# PCM3060_Guitar_Cape.net
KiCad netlist of a schematic drawn in EAGLE
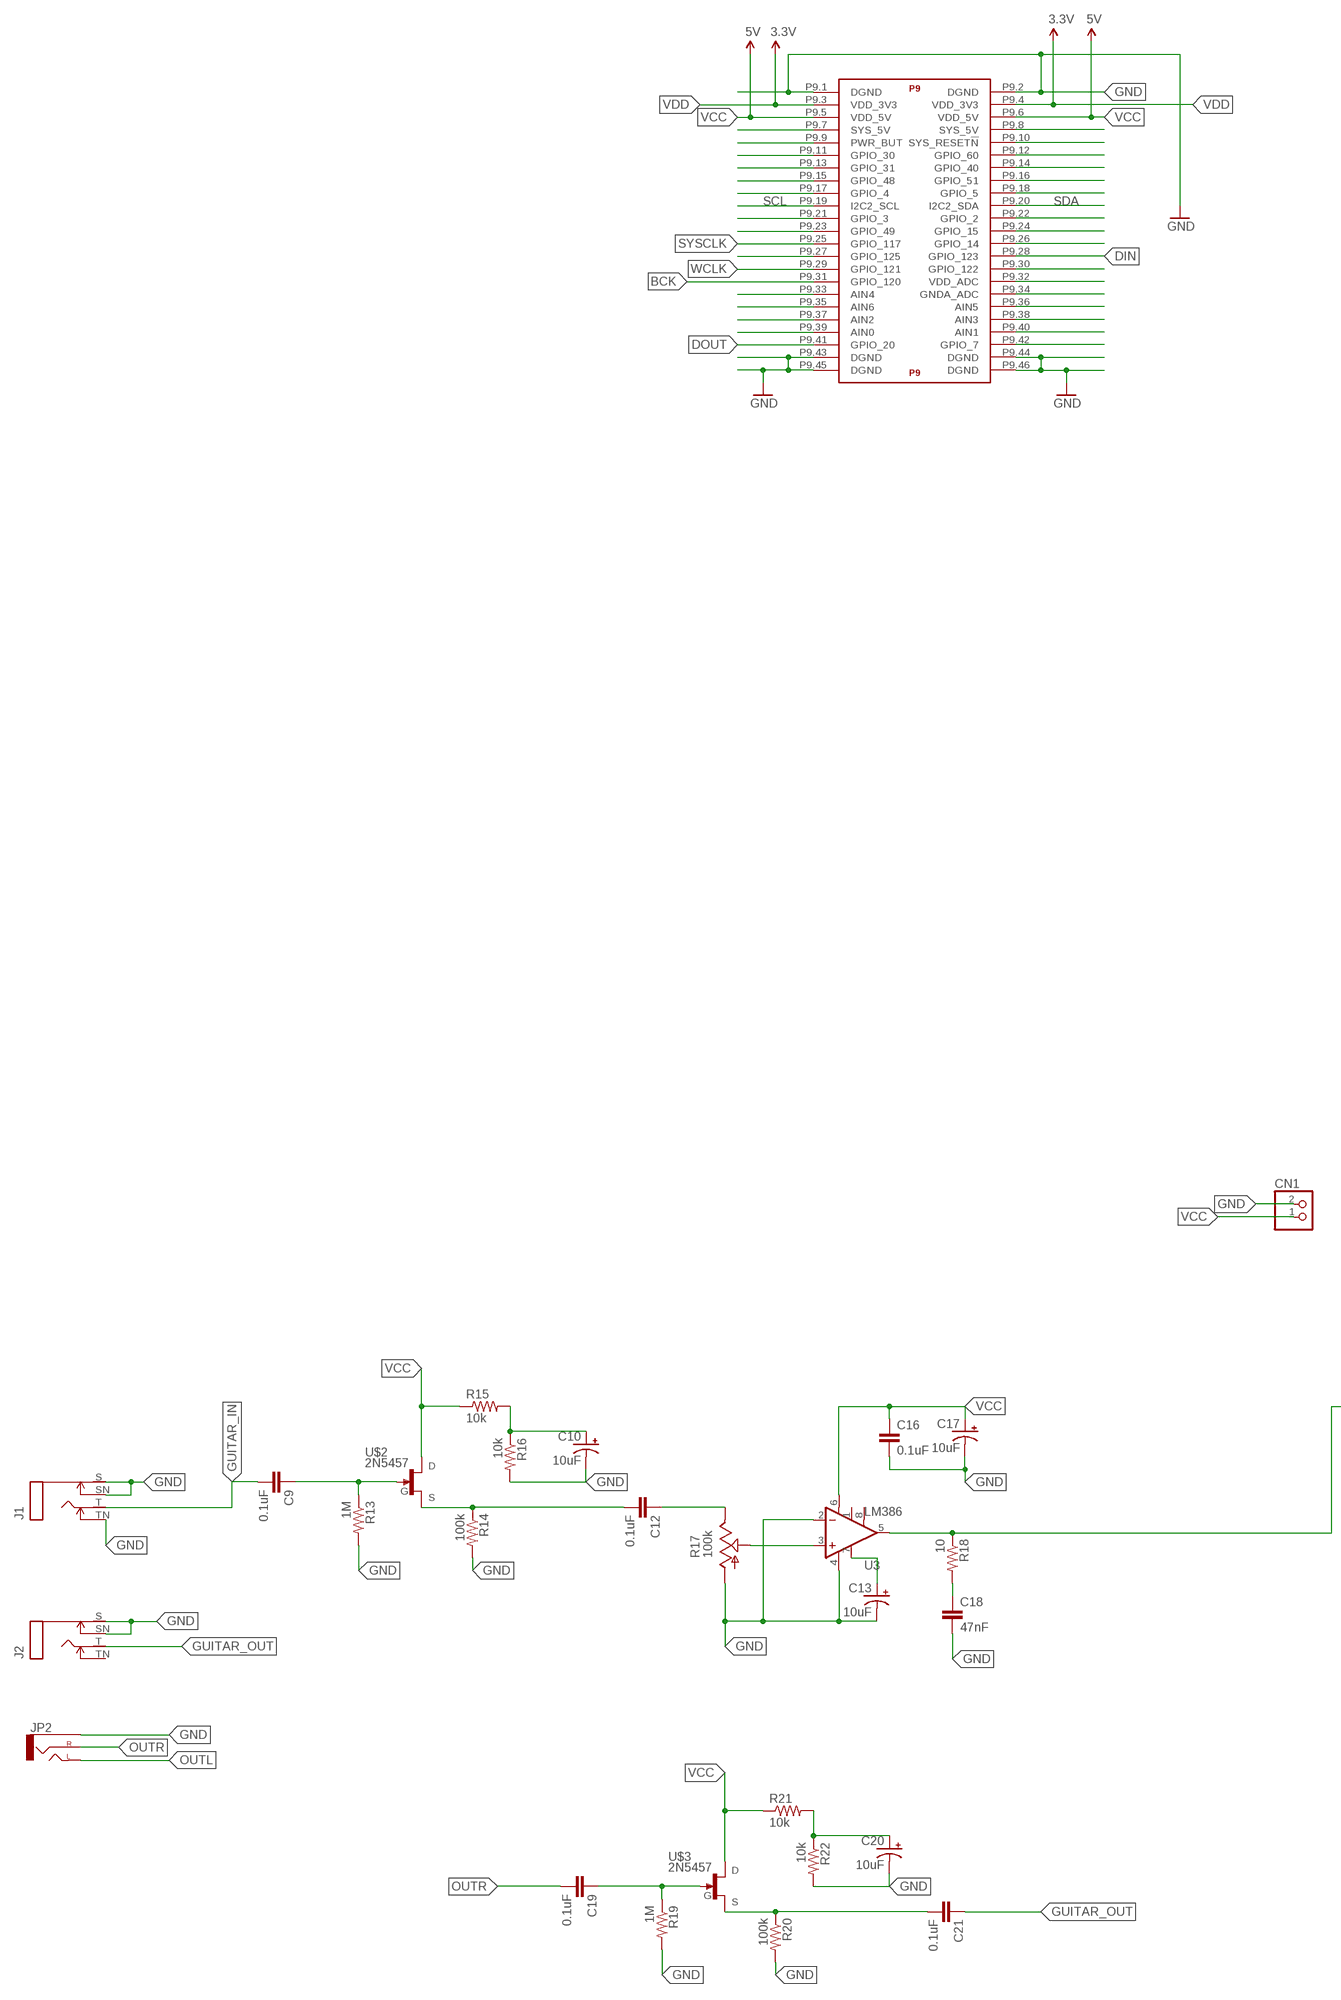
[diagram p0: schematic, sheet 1, part 1 of 2]
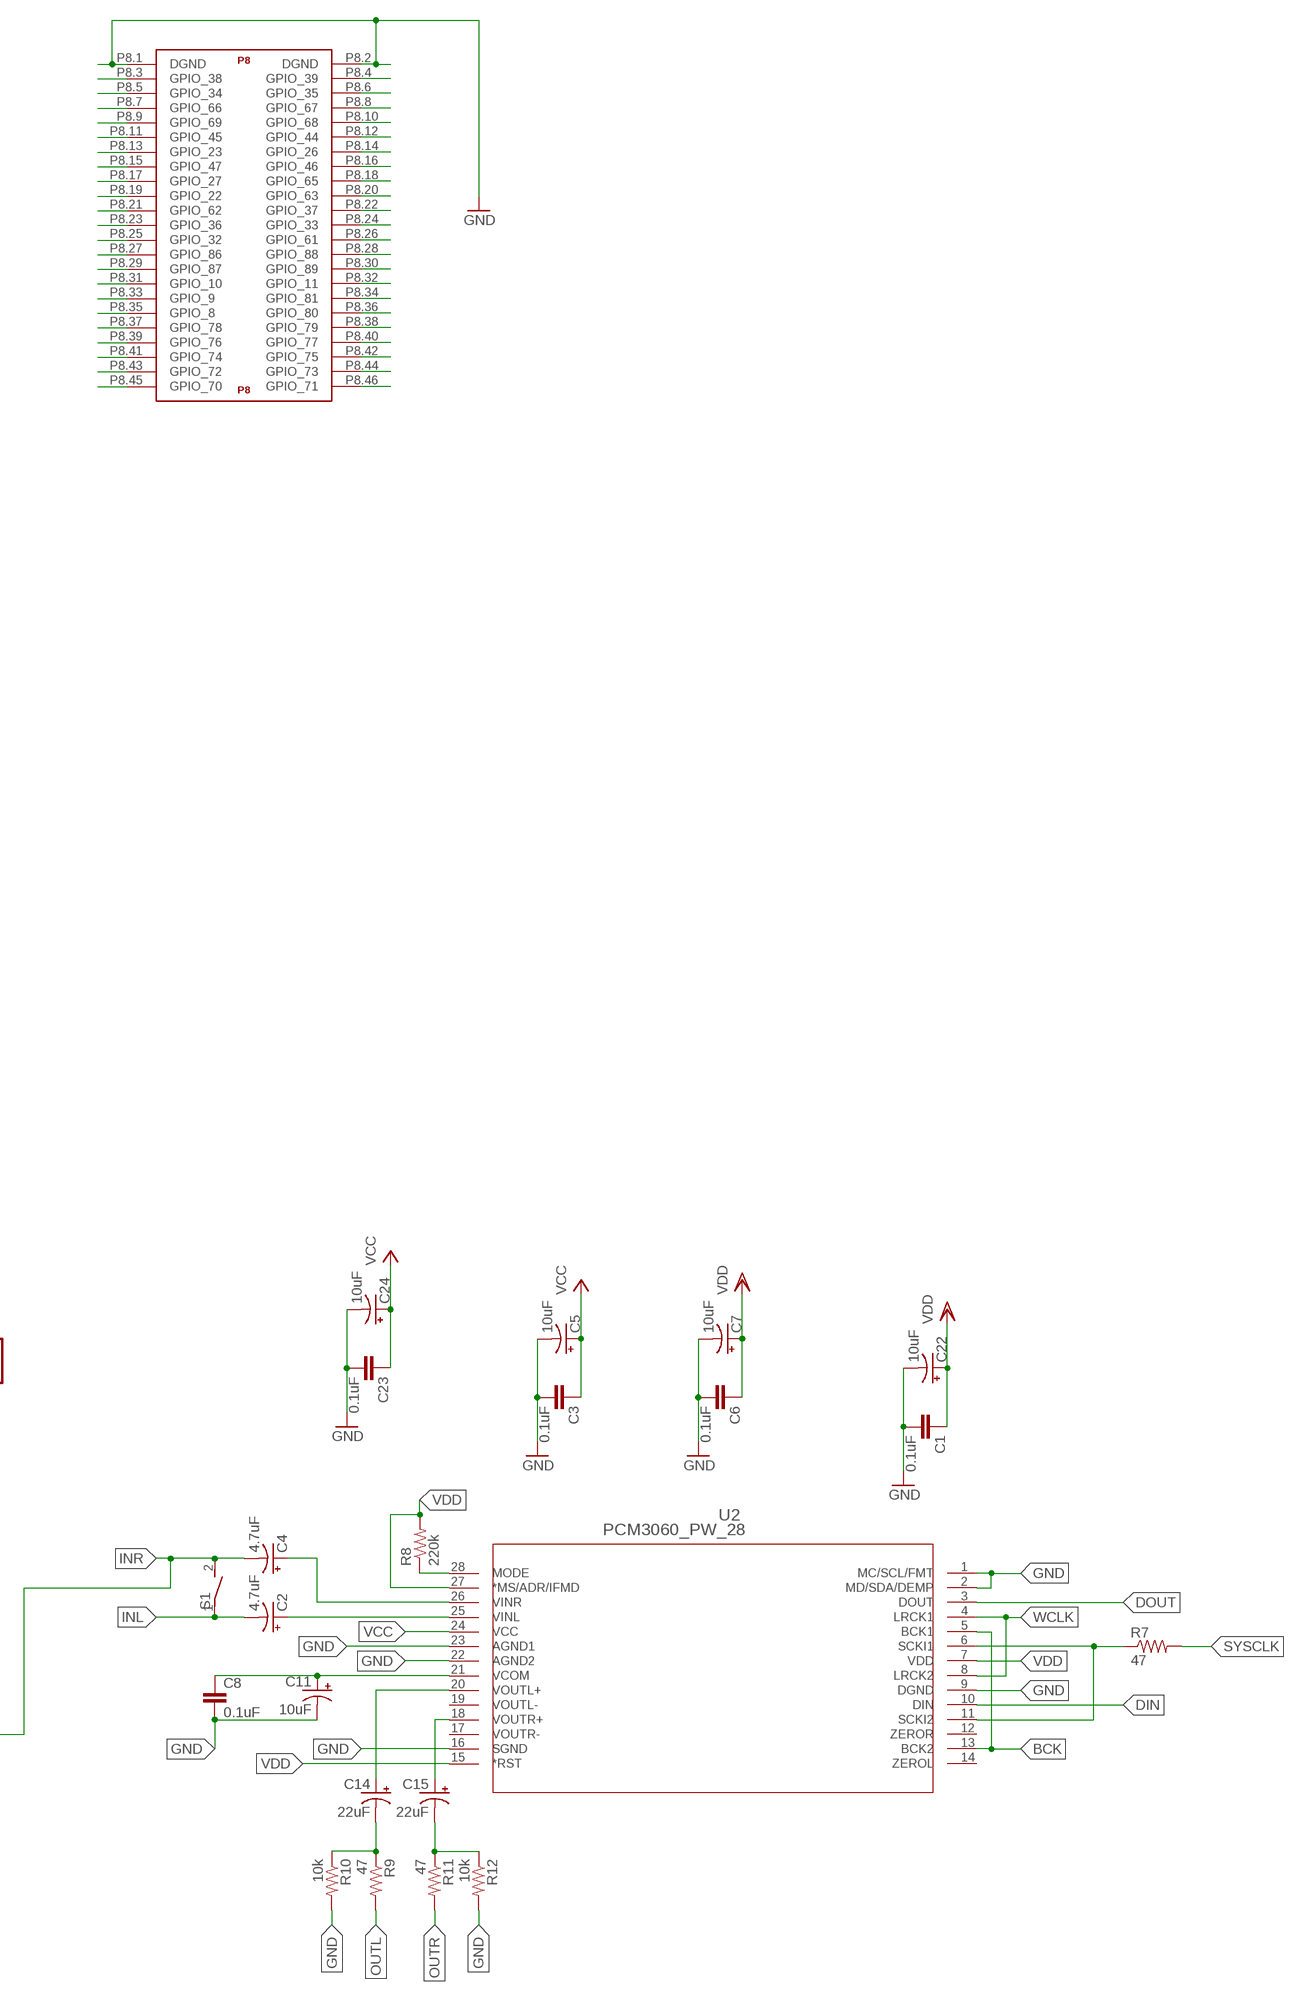
[diagram p1: schematic, sheet 1, part 2 of 2]

(export (version "E")
  (design (tool "Eeschema 10.0.6"))
  (components
    (comp (ref "C1")
      (value "0.1uF")
      (footprint "eagle-import:0603-CAP")
      (libsource (lib "eagle-import") (part "0.1UF-25V-5%(0603)"))
    )
    (comp (ref "C2")
      (value "4.7uF")
      (footprint "eagle-import:CPOL-RADIAL-10UF-25V")
      (libsource (lib "eagle-import") (part "CAP_POLPTH2"))
    )
    (comp (ref "C3")
      (value "0.1uF")
      (footprint "eagle-import:0603-CAP")
      (libsource (lib "eagle-import") (part "0.1UF-25V-5%(0603)"))
    )
    (comp (ref "C4")
      (value "4.7uF")
      (footprint "eagle-import:CPOL-RADIAL-10UF-25V")
      (libsource (lib "eagle-import") (part "CAP_POLPTH2"))
    )
    (comp (ref "C5")
      (value "10uF")
      (footprint "eagle-import:CPOL-RADIAL-10UF-25V")
      (libsource (lib "eagle-import") (part "CAP_POLPTH2"))
    )
    (comp (ref "C6")
      (value "0.1uF")
      (footprint "eagle-import:0603-CAP")
      (libsource (lib "eagle-import") (part "0.1UF-25V-5%(0603)"))
    )
    (comp (ref "C7")
      (value "10uF")
      (footprint "eagle-import:CPOL-RADIAL-10UF-25V")
      (libsource (lib "eagle-import") (part "CAP_POLPTH2"))
    )
    (comp (ref "C8")
      (value "0.1uF")
      (footprint "eagle-import:0603-CAP")
      (libsource (lib "eagle-import") (part "0.1UF-25V-5%(0603)"))
    )
    (comp (ref "C9")
      (value "0.1uF")
      (footprint "eagle-import:0603-CAP")
      (libsource (lib "eagle-import") (part "0.1UF-25V-5%(0603)"))
    )
    (comp (ref "C10")
      (value "10uF")
      (footprint "eagle-import:CPOL-RADIAL-10UF-25V")
      (libsource (lib "eagle-import") (part "CAP_POLPTH2"))
    )
    (comp (ref "C11")
      (value "10uF")
      (footprint "eagle-import:CPOL-RADIAL-10UF-25V")
      (libsource (lib "eagle-import") (part "CAP_POLPTH2"))
    )
    (comp (ref "C12")
      (value "0.1uF")
      (footprint "eagle-import:0603-CAP")
      (libsource (lib "eagle-import") (part "0.1UF-25V-5%(0603)"))
    )
    (comp (ref "C13")
      (value "10uF")
      (footprint "eagle-import:CPOL-RADIAL-10UF-25V")
      (libsource (lib "eagle-import") (part "CAP_POLPTH2"))
    )
    (comp (ref "C14")
      (value "22uF")
      (footprint "eagle-import:CPOL-RADIAL-10UF-25V")
      (libsource (lib "eagle-import") (part "CAP_POLPTH2"))
    )
    (comp (ref "C15")
      (value "22uF")
      (footprint "eagle-import:CPOL-RADIAL-10UF-25V")
      (libsource (lib "eagle-import") (part "CAP_POLPTH2"))
    )
    (comp (ref "C16")
      (value "0.1uF")
      (footprint "eagle-import:0603-CAP")
      (libsource (lib "eagle-import") (part "0.1UF-25V-5%(0603)"))
    )
    (comp (ref "C17")
      (value "10uF")
      (footprint "eagle-import:CPOL-RADIAL-10UF-25V")
      (libsource (lib "eagle-import") (part "CAP_POLPTH2"))
    )
    (comp (ref "C18")
      (value "47nF")
      (footprint "eagle-import:0603-CAP")
      (libsource (lib "eagle-import") (part "47NF(0.047UF/47000PF)-25V-5%(0603)SMD"))
    )
    (comp (ref "C19")
      (value "0.1uF")
      (footprint "eagle-import:0603-CAP")
      (libsource (lib "eagle-import") (part "0.1UF-25V-5%(0603)"))
    )
    (comp (ref "C20")
      (value "10uF")
      (footprint "eagle-import:CPOL-RADIAL-10UF-25V")
      (libsource (lib "eagle-import") (part "CAP_POLPTH2"))
    )
    (comp (ref "C21")
      (value "0.1uF")
      (footprint "eagle-import:0603-CAP")
      (libsource (lib "eagle-import") (part "0.1UF-25V-5%(0603)"))
    )
    (comp (ref "C22")
      (value "10uF")
      (footprint "eagle-import:CPOL-RADIAL-10UF-25V")
      (libsource (lib "eagle-import") (part "CAP_POLPTH2"))
    )
    (comp (ref "C23")
      (value "0.1uF")
      (footprint "eagle-import:0603-CAP")
      (libsource (lib "eagle-import") (part "0.1UF-25V-5%(0603)"))
    )
    (comp (ref "C24")
      (value "10uF")
      (footprint "eagle-import:CPOL-RADIAL-10UF-25V")
      (libsource (lib "eagle-import") (part "CAP_POLPTH2"))
    )
    (comp (ref "CN1")
      (value "JST_2PIN-THM")
      (footprint "eagle-import:JST-PH-2-THM")
      (libsource (lib "eagle-import") (part "JST_2PIN-THM"))
    )
    (comp (ref "J1")
      (value "MONOSW")
      (footprint "eagle-import:NMJ4HCD2")
      (libsource (lib "eagle-import") (part "MONOSW"))
    )
    (comp (ref "J2")
      (value "MONOSW")
      (footprint "eagle-import:NMJ4HCD2")
      (libsource (lib "eagle-import") (part "MONOSW"))
    )
    (comp (ref "JP2")
      (value "AUDIO-JACK2.5MM")
      (footprint "eagle-import:STEREOJACK2.5MM_STEREOJACK2.5MM")
      (libsource (lib "eagle-import") (part "AUDIO-JACK2.5MM"))
    )
    (comp (ref "R7")
      (value "47")
      (footprint "eagle-import:1206")
      (libsource (lib "eagle-import") (part "RESISTOR1206"))
    )
    (comp (ref "R8")
      (value "220k")
      (footprint "eagle-import:1206")
      (libsource (lib "eagle-import") (part "RESISTOR1206"))
    )
    (comp (ref "R9")
      (value "47")
      (footprint "eagle-import:1206")
      (libsource (lib "eagle-import") (part "RESISTOR1206"))
    )
    (comp (ref "R10")
      (value "10k")
      (footprint "eagle-import:1206")
      (libsource (lib "eagle-import") (part "RESISTOR1206"))
    )
    (comp (ref "R11")
      (value "47")
      (footprint "eagle-import:1206")
      (libsource (lib "eagle-import") (part "RESISTOR1206"))
    )
    (comp (ref "R12")
      (value "10k")
      (footprint "eagle-import:1206")
      (libsource (lib "eagle-import") (part "RESISTOR1206"))
    )
    (comp (ref "R13")
      (value "1M")
      (footprint "eagle-import:1206")
      (libsource (lib "eagle-import") (part "RESISTOR1206"))
    )
    (comp (ref "R14")
      (value "100k")
      (footprint "eagle-import:1206")
      (libsource (lib "eagle-import") (part "RESISTOR1206"))
    )
    (comp (ref "R15")
      (value "10k")
      (footprint "eagle-import:1206")
      (libsource (lib "eagle-import") (part "RESISTOR1206"))
    )
    (comp (ref "R16")
      (value "10k")
      (footprint "eagle-import:1206")
      (libsource (lib "eagle-import") (part "RESISTOR1206"))
    )
    (comp (ref "R17")
      (value "100k")
      (footprint "eagle-import:RJ9W")
      (libsource (lib "eagle-import") (part "TRIM_US-RJ9W"))
    )
    (comp (ref "R18")
      (value "10")
      (footprint "eagle-import:1206")
      (libsource (lib "eagle-import") (part "RESISTOR1206"))
    )
    (comp (ref "R19")
      (value "1M")
      (footprint "eagle-import:1206")
      (libsource (lib "eagle-import") (part "RESISTOR1206"))
    )
    (comp (ref "R20")
      (value "100k")
      (footprint "eagle-import:1206")
      (libsource (lib "eagle-import") (part "RESISTOR1206"))
    )
    (comp (ref "R21")
      (value "10k")
      (footprint "eagle-import:1206")
      (libsource (lib "eagle-import") (part "RESISTOR1206"))
    )
    (comp (ref "R22")
      (value "10k")
      (footprint "eagle-import:1206")
      (libsource (lib "eagle-import") (part "RESISTOR1206"))
    )
    (comp (ref "S1")
      (value "DS01E")
      (footprint "eagle-import:DS-01")
      (libsource (lib "eagle-import") (part "DS01E"))
    )
    (comp (ref "U$1")
      (value "BEAGLE_BONE_BLACK_CAPE")
      (footprint "eagle-import:BEAGLE_BONE_BLACK_CAPE")
      (libsource (lib "eagle-import") (part "BEAGLE_BONE_BLACK_CAPE"))
    )
    (comp (ref "U$2")
      (value "2N5457")
      (footprint "eagle-import:TO-92")
      (libsource (lib "eagle-import") (part "2N5457"))
    )
    (comp (ref "U$3")
      (value "2N5457")
      (footprint "eagle-import:TO-92")
      (libsource (lib "eagle-import") (part "2N5457"))
    )
    (comp (ref "U2")
      (value "PCM3060_PW_28")
      (footprint "eagle-import:PW28")
      (fields
        (field (name "GENERIC_PART_NUMBER") "PCM3060")
        (field (name "MANUFACTURER") "Texas Instruments")
        (field (name "MANUFACTURER_PART_NUMBER") "pcm3060_pw_28")
      )
      (libsource (lib "eagle-import") (part "PCM3060_PW_28"))
    )
    (comp (ref "U3")
      (value "LM386")
      (footprint "eagle-import:DIP08")
      (libsource (lib "eagle-import") (part "LM386"))
    )
  )
  (nets
    (net (code "1") (name "/SCL") (class "Default")
      (node (ref "U$1") (pin "P9.19") (pinfunction "I2C2_SCL_P9.19") (pintype "bidirectional"))
    )
    (net (code "2") (name "/SDA") (class "Default")
      (node (ref "U$1") (pin "P9.20") (pinfunction "I2C2_SDA_P9.20") (pintype "bidirectional"))
    )
    (net (code "3") (name "BCK") (class "Default")
      (node (ref "U$1") (pin "P9.31") (pinfunction "GPIO_120_P9.31") (pintype "bidirectional"))
      (node (ref "U2") (pin "13") (pinfunction "BCK2_13") (pintype "bidirectional"))
      (node (ref "U2") (pin "5") (pinfunction "BCK1_5") (pintype "bidirectional"))
    )
    (net (code "4") (name "DIN") (class "Default")
      (node (ref "U$1") (pin "P9.28") (pinfunction "GPIO_123_P9.28") (pintype "bidirectional"))
      (node (ref "U2") (pin "10") (pinfunction "DIN_10") (pintype "input"))
    )
    (net (code "5") (name "DOUT") (class "Default")
      (node (ref "U$1") (pin "P9.41") (pinfunction "GPIO_20_P9.41") (pintype "bidirectional"))
      (node (ref "U2") (pin "3") (pinfunction "DOUT_3") (pintype "output"))
    )
    (net (code "6") (name "GND") (class "Default")
      (node (ref "C1") (pin "2") (pinfunction "2_2") (pintype "passive"))
      (node (ref "C10") (pin "2") (pinfunction "-_2") (pintype "passive"))
      (node (ref "C11") (pin "2") (pinfunction "-_2") (pintype "passive"))
      (node (ref "C13") (pin "2") (pinfunction "-_2") (pintype "passive"))
      (node (ref "C16") (pin "2") (pinfunction "2_2") (pintype "passive"))
      (node (ref "C17") (pin "2") (pinfunction "-_2") (pintype "passive"))
      (node (ref "C18") (pin "2") (pinfunction "2_2") (pintype "passive"))
      (node (ref "C20") (pin "2") (pinfunction "-_2") (pintype "passive"))
      (node (ref "C22") (pin "2") (pinfunction "-_2") (pintype "passive"))
      (node (ref "C23") (pin "2") (pinfunction "2_2") (pintype "passive"))
      (node (ref "C24") (pin "2") (pinfunction "-_2") (pintype "passive"))
      (node (ref "C3") (pin "2") (pinfunction "2_2") (pintype "passive"))
      (node (ref "C5") (pin "2") (pinfunction "-_2") (pintype "passive"))
      (node (ref "C6") (pin "2") (pinfunction "2_2") (pintype "passive"))
      (node (ref "C7") (pin "2") (pinfunction "-_2") (pintype "passive"))
      (node (ref "C8") (pin "2") (pinfunction "2_2") (pintype "passive"))
      (node (ref "CN1") (pin "2") (pinfunction "1_2") (pintype "passive"))
      (node (ref "J1") (pin "S") (pinfunction "S_S") (pintype "passive"))
      (node (ref "J1") (pin "SN") (pinfunction "SN_SN") (pintype "passive"))
      (node (ref "J1") (pin "TN") (pinfunction "TN_TN") (pintype "passive"))
      (node (ref "J2") (pin "S") (pinfunction "S_S") (pintype "passive"))
      (node (ref "J2") (pin "SN") (pinfunction "SN_SN") (pintype "passive"))
      (node (ref "JP2") (pin "RING1") (pinfunction "SLEEVE_RING1") (pintype "bidirectional"))
      (node (ref "R10") (pin "2") (pinfunction "2_2") (pintype "passive"))
      (node (ref "R12") (pin "2") (pinfunction "2_2") (pintype "passive"))
      (node (ref "R13") (pin "2") (pinfunction "2_2") (pintype "passive"))
      (node (ref "R14") (pin "2") (pinfunction "2_2") (pintype "passive"))
      (node (ref "R16") (pin "2") (pinfunction "2_2") (pintype "passive"))
      (node (ref "R17") (pin "A") (pinfunction "A_A") (pintype "passive"))
      (node (ref "R19") (pin "2") (pinfunction "2_2") (pintype "passive"))
      (node (ref "R20") (pin "2") (pinfunction "2_2") (pintype "passive"))
      (node (ref "R22") (pin "2") (pinfunction "2_2") (pintype "passive"))
      (node (ref "U$1") (pin "P8.1") (pinfunction "DGND_P8.1") (pintype "bidirectional"))
      (node (ref "U$1") (pin "P8.2") (pinfunction "DGND_P8.2") (pintype "bidirectional"))
      (node (ref "U$1") (pin "P9.1") (pinfunction "DGND_P9.1") (pintype "bidirectional"))
      (node (ref "U$1") (pin "P9.2") (pinfunction "DGND_P9.2") (pintype "bidirectional"))
      (node (ref "U$1") (pin "P9.43") (pinfunction "DGND_P9.43") (pintype "bidirectional"))
      (node (ref "U$1") (pin "P9.44") (pinfunction "DGND_P9.44") (pintype "bidirectional"))
      (node (ref "U$1") (pin "P9.45") (pinfunction "DGND_P9.45") (pintype "bidirectional"))
      (node (ref "U$1") (pin "P9.46") (pinfunction "DGND_P9.46") (pintype "bidirectional"))
      (node (ref "U2") (pin "1") (pinfunction "MC/SCL/FMT_1") (pintype "input"))
      (node (ref "U2") (pin "16") (pinfunction "SGND_16") (pintype "power_in"))
      (node (ref "U2") (pin "2") (pinfunction "MD/SDA/DEMP_2") (pintype "bidirectional"))
      (node (ref "U2") (pin "22") (pinfunction "AGND2_22") (pintype "power_in"))
      (node (ref "U2") (pin "23") (pinfunction "AGND1_23") (pintype "power_in"))
      (node (ref "U2") (pin "9") (pinfunction "DGND_9") (pintype "power_in"))
      (node (ref "U3") (pin "2") (pinfunction "-IN_2") (pintype "input"))
      (node (ref "U3") (pin "4") (pinfunction "V-_4") (pintype "power_in"))
    )
    (net (code "7") (name "GUITAR_IN") (class "Default")
      (node (ref "C9") (pin "2") (pinfunction "2_2") (pintype "passive"))
      (node (ref "J1") (pin "T") (pinfunction "T_T") (pintype "passive"))
    )
    (net (code "8") (name "GUITAR_OUT") (class "Default")
      (node (ref "C21") (pin "1") (pinfunction "1_1") (pintype "passive"))
      (node (ref "J2") (pin "T") (pinfunction "T_T") (pintype "passive"))
    )
    (net (code "9") (name "INL") (class "Default")
      (node (ref "C2") (pin "2") (pinfunction "-_2") (pintype "passive"))
      (node (ref "S1") (pin "1") (pinfunction "1_1") (pintype "passive"))
    )
    (net (code "10") (name "INR") (class "Default")
      (node (ref "C4") (pin "2") (pinfunction "-_2") (pintype "passive"))
      (node (ref "R18") (pin "1") (pinfunction "1_1") (pintype "passive"))
      (node (ref "S1") (pin "2") (pinfunction "2_2") (pintype "passive"))
      (node (ref "U3") (pin "5") (pinfunction "OUT_5") (pintype "output"))
    )
    (net (code "11") (name "Net-(C2-+)") (class "Default")
      (node (ref "C2") (pin "1") (pinfunction "+_1") (pintype "passive"))
      (node (ref "U2") (pin "25") (pinfunction "VINL_25") (pintype "input"))
    )
    (net (code "12") (name "Net-(C4-+)") (class "Default")
      (node (ref "C4") (pin "1") (pinfunction "+_1") (pintype "passive"))
      (node (ref "U2") (pin "26") (pinfunction "VINR_26") (pintype "input"))
    )
    (net (code "13") (name "Net-(C10-+)") (class "Default")
      (node (ref "C10") (pin "1") (pinfunction "+_1") (pintype "passive"))
      (node (ref "R15") (pin "2") (pinfunction "2_2") (pintype "passive"))
      (node (ref "R16") (pin "1") (pinfunction "1_1") (pintype "passive"))
    )
    (net (code "14") (name "Net-(C11-+)") (class "Default")
      (node (ref "C11") (pin "1") (pinfunction "+_1") (pintype "passive"))
      (node (ref "C8") (pin "1") (pinfunction "1_1") (pintype "passive"))
      (node (ref "U2") (pin "21") (pinfunction "VCOM_21") (pintype "power_in"))
    )
    (net (code "15") (name "Net-(C12-Pad1)") (class "Default")
      (node (ref "C12") (pin "1") (pinfunction "1_1") (pintype "passive"))
      (node (ref "R17") (pin "E") (pinfunction "E_E") (pintype "passive"))
    )
    (net (code "16") (name "Net-(C13-+)") (class "Default")
      (node (ref "C13") (pin "1") (pinfunction "+_1") (pintype "passive"))
      (node (ref "U3") (pin "7") (pinfunction "BP_7") (pintype "bidirectional"))
    )
    (net (code "17") (name "Net-(C14-+)") (class "Default")
      (node (ref "C14") (pin "1") (pinfunction "+_1") (pintype "passive"))
      (node (ref "U2") (pin "20") (pinfunction "VOUTL+_20") (pintype "output"))
    )
    (net (code "18") (name "Net-(C14--)") (class "Default")
      (node (ref "C14") (pin "2") (pinfunction "-_2") (pintype "passive"))
      (node (ref "R10") (pin "1") (pinfunction "1_1") (pintype "passive"))
      (node (ref "R9") (pin "1") (pinfunction "1_1") (pintype "passive"))
    )
    (net (code "19") (name "Net-(C15-+)") (class "Default")
      (node (ref "C15") (pin "1") (pinfunction "+_1") (pintype "passive"))
      (node (ref "U2") (pin "18") (pinfunction "VOUTR+_18") (pintype "output"))
    )
    (net (code "20") (name "Net-(C15--)") (class "Default")
      (node (ref "C15") (pin "2") (pinfunction "-_2") (pintype "passive"))
      (node (ref "R11") (pin "1") (pinfunction "1_1") (pintype "passive"))
      (node (ref "R12") (pin "1") (pinfunction "1_1") (pintype "passive"))
    )
    (net (code "21") (name "Net-(C18-Pad1)") (class "Default")
      (node (ref "C18") (pin "1") (pinfunction "1_1") (pintype "passive"))
      (node (ref "R18") (pin "2") (pinfunction "2_2") (pintype "passive"))
    )
    (net (code "22") (name "Net-(C20-+)") (class "Default")
      (node (ref "C20") (pin "1") (pinfunction "+_1") (pintype "passive"))
      (node (ref "R21") (pin "2") (pinfunction "2_2") (pintype "passive"))
      (node (ref "R22") (pin "1") (pinfunction "1_1") (pintype "passive"))
    )
    (net (code "23") (name "Net-(U$2-G)") (class "Default")
      (node (ref "C9") (pin "1") (pinfunction "1_1") (pintype "passive"))
      (node (ref "R13") (pin "1") (pinfunction "1_1") (pintype "passive"))
      (node (ref "U$2") (pin "3") (pinfunction "G_3") (pintype "passive"))
    )
    (net (code "24") (name "Net-(U$2-S)") (class "Default")
      (node (ref "C12") (pin "2") (pinfunction "2_2") (pintype "passive"))
      (node (ref "R14") (pin "1") (pinfunction "1_1") (pintype "passive"))
      (node (ref "U$2") (pin "2") (pinfunction "S_2") (pintype "passive"))
    )
    (net (code "25") (name "Net-(U$3-G)") (class "Default")
      (node (ref "C19") (pin "1") (pinfunction "1_1") (pintype "passive"))
      (node (ref "R19") (pin "1") (pinfunction "1_1") (pintype "passive"))
      (node (ref "U$3") (pin "3") (pinfunction "G_3") (pintype "passive"))
    )
    (net (code "26") (name "Net-(U$3-S)") (class "Default")
      (node (ref "C21") (pin "2") (pinfunction "2_2") (pintype "passive"))
      (node (ref "R20") (pin "1") (pinfunction "1_1") (pintype "passive"))
      (node (ref "U$3") (pin "2") (pinfunction "S_2") (pintype "passive"))
    )
    (net (code "27") (name "Net-(U2-MODE)") (class "Default")
      (node (ref "R8") (pin "1") (pinfunction "1_1") (pintype "passive"))
      (node (ref "U2") (pin "28") (pinfunction "MODE_28") (pintype "input"))
    )
    (net (code "28") (name "Net-(U2-SCKI1)") (class "Default")
      (node (ref "R7") (pin "1") (pinfunction "1_1") (pintype "passive"))
      (node (ref "U2") (pin "11") (pinfunction "SCKI2_11") (pintype "bidirectional"))
      (node (ref "U2") (pin "6") (pinfunction "SCKI1_6") (pintype "input"))
    )
    (net (code "29") (name "Net-(U3-+IN)") (class "Default")
      (node (ref "R17") (pin "S") (pinfunction "S_S") (pintype "passive"))
      (node (ref "U3") (pin "3") (pinfunction "+IN_3") (pintype "input"))
    )
    (net (code "30") (name "OUTL") (class "Default")
      (node (ref "JP2") (pin "SHIELD") (pinfunction "LEFT_SHIELD") (pintype "bidirectional"))
      (node (ref "R9") (pin "2") (pinfunction "2_2") (pintype "passive"))
    )
    (net (code "31") (name "OUTR") (class "Default")
      (node (ref "C19") (pin "2") (pinfunction "2_2") (pintype "passive"))
      (node (ref "JP2") (pin "TIP") (pinfunction "RIGHT_TIP") (pintype "bidirectional"))
      (node (ref "R11") (pin "2") (pinfunction "2_2") (pintype "passive"))
    )
    (net (code "32") (name "SYSCLK") (class "Default")
      (node (ref "R7") (pin "2") (pinfunction "2_2") (pintype "passive"))
      (node (ref "U$1") (pin "P9.25") (pinfunction "GPIO_117_P9.25") (pintype "bidirectional"))
    )
    (net (code "33") (name "VCC") (class "Default")
      (node (ref "C16") (pin "1") (pinfunction "1_1") (pintype "passive"))
      (node (ref "C17") (pin "1") (pinfunction "+_1") (pintype "passive"))
      (node (ref "C23") (pin "1") (pinfunction "1_1") (pintype "passive"))
      (node (ref "C24") (pin "1") (pinfunction "+_1") (pintype "passive"))
      (node (ref "C3") (pin "1") (pinfunction "1_1") (pintype "passive"))
      (node (ref "C5") (pin "1") (pinfunction "+_1") (pintype "passive"))
      (node (ref "CN1") (pin "1") (pinfunction "2_1") (pintype "passive"))
      (node (ref "R15") (pin "1") (pinfunction "1_1") (pintype "passive"))
      (node (ref "R21") (pin "1") (pinfunction "1_1") (pintype "passive"))
      (node (ref "U$1") (pin "P9.5") (pinfunction "VDD_5V_P9.5") (pintype "bidirectional"))
      (node (ref "U$1") (pin "P9.6") (pinfunction "VDD_5V_P9.6") (pintype "bidirectional"))
      (node (ref "U$2") (pin "1") (pinfunction "D_1") (pintype "passive"))
      (node (ref "U$3") (pin "1") (pinfunction "D_1") (pintype "passive"))
      (node (ref "U2") (pin "24") (pinfunction "VCC_24") (pintype "power_in"))
      (node (ref "U3") (pin "6") (pinfunction "V+_6") (pintype "power_in"))
    )
    (net (code "34") (name "VDD") (class "Default")
      (node (ref "C1") (pin "1") (pinfunction "1_1") (pintype "passive"))
      (node (ref "C22") (pin "1") (pinfunction "+_1") (pintype "passive"))
      (node (ref "C6") (pin "1") (pinfunction "1_1") (pintype "passive"))
      (node (ref "C7") (pin "1") (pinfunction "+_1") (pintype "passive"))
      (node (ref "R8") (pin "2") (pinfunction "2_2") (pintype "passive"))
      (node (ref "U$1") (pin "P9.3") (pinfunction "VDD_3V3_P9.3") (pintype "bidirectional"))
      (node (ref "U$1") (pin "P9.4") (pinfunction "VDD_3V3_P9.4") (pintype "bidirectional"))
      (node (ref "U2") (pin "15") (pinfunction "*RST_15") (pintype "input"))
      (node (ref "U2") (pin "27") (pinfunction "*MS/ADR/IFMD_27") (pintype "input"))
      (node (ref "U2") (pin "7") (pinfunction "VDD_7") (pintype "power_in"))
    )
    (net (code "35") (name "WCLK") (class "Default")
      (node (ref "U$1") (pin "P9.29") (pinfunction "GPIO_121_P9.29") (pintype "bidirectional"))
      (node (ref "U2") (pin "4") (pinfunction "LRCK1_4") (pintype "bidirectional"))
      (node (ref "U2") (pin "8") (pinfunction "LRCK2_8") (pintype "bidirectional"))
    )
    (net (code "36") (name "unconnected-(J2-PadTN)") (class "Default")
      (node (ref "J2") (pin "TN") (pinfunction "TN_TN") (pintype "passive"))
    )
    (net (code "37") (name "unconnected-(U$1A-GPIO_8-PadP8.35)") (class "Default")
      (node (ref "U$1") (pin "P8.35") (pinfunction "GPIO_8_P8.35") (pintype "bidirectional"))
    )
    (net (code "38") (name "unconnected-(U$1A-GPIO_9-PadP8.33)") (class "Default")
      (node (ref "U$1") (pin "P8.33") (pinfunction "GPIO_9_P8.33") (pintype "bidirectional"))
    )
    (net (code "39") (name "unconnected-(U$1A-GPIO_10-PadP8.31)") (class "Default")
      (node (ref "U$1") (pin "P8.31") (pinfunction "GPIO_10_P8.31") (pintype "bidirectional"))
    )
    (net (code "40") (name "unconnected-(U$1A-GPIO_11-PadP8.32)") (class "Default")
      (node (ref "U$1") (pin "P8.32") (pinfunction "GPIO_11_P8.32") (pintype "bidirectional"))
    )
    (net (code "41") (name "unconnected-(U$1A-GPIO_22-PadP8.19)") (class "Default")
      (node (ref "U$1") (pin "P8.19") (pinfunction "GPIO_22_P8.19") (pintype "bidirectional"))
    )
    (net (code "42") (name "unconnected-(U$1A-GPIO_23-PadP8.13)") (class "Default")
      (node (ref "U$1") (pin "P8.13") (pinfunction "GPIO_23_P8.13") (pintype "bidirectional"))
    )
    (net (code "43") (name "unconnected-(U$1A-GPIO_26-PadP8.14)") (class "Default")
      (node (ref "U$1") (pin "P8.14") (pinfunction "GPIO_26_P8.14") (pintype "bidirectional"))
    )
    (net (code "44") (name "unconnected-(U$1A-GPIO_27-PadP8.17)") (class "Default")
      (node (ref "U$1") (pin "P8.17") (pinfunction "GPIO_27_P8.17") (pintype "bidirectional"))
    )
    (net (code "45") (name "unconnected-(U$1A-GPIO_32-PadP8.25)") (class "Default")
      (node (ref "U$1") (pin "P8.25") (pinfunction "GPIO_32_P8.25") (pintype "bidirectional"))
    )
    (net (code "46") (name "unconnected-(U$1A-GPIO_33-PadP8.24)") (class "Default")
      (node (ref "U$1") (pin "P8.24") (pinfunction "GPIO_33_P8.24") (pintype "bidirectional"))
    )
    (net (code "47") (name "unconnected-(U$1A-GPIO_34-PadP8.5)") (class "Default")
      (node (ref "U$1") (pin "P8.5") (pinfunction "GPIO_34_P8.5") (pintype "bidirectional"))
    )
    (net (code "48") (name "unconnected-(U$1A-GPIO_35-PadP8.6)") (class "Default")
      (node (ref "U$1") (pin "P8.6") (pinfunction "GPIO_35_P8.6") (pintype "bidirectional"))
    )
    (net (code "49") (name "unconnected-(U$1A-GPIO_36-PadP8.23)") (class "Default")
      (node (ref "U$1") (pin "P8.23") (pinfunction "GPIO_36_P8.23") (pintype "bidirectional"))
    )
    (net (code "50") (name "unconnected-(U$1A-GPIO_37-PadP8.22)") (class "Default")
      (node (ref "U$1") (pin "P8.22") (pinfunction "GPIO_37_P8.22") (pintype "bidirectional"))
    )
    (net (code "51") (name "unconnected-(U$1A-GPIO_38-PadP8.3)") (class "Default")
      (node (ref "U$1") (pin "P8.3") (pinfunction "GPIO_38_P8.3") (pintype "bidirectional"))
    )
    (net (code "52") (name "unconnected-(U$1A-GPIO_39-PadP8.4)") (class "Default")
      (node (ref "U$1") (pin "P8.4") (pinfunction "GPIO_39_P8.4") (pintype "bidirectional"))
    )
    (net (code "53") (name "unconnected-(U$1A-GPIO_44-PadP8.12)") (class "Default")
      (node (ref "U$1") (pin "P8.12") (pinfunction "GPIO_44_P8.12") (pintype "bidirectional"))
    )
    (net (code "54") (name "unconnected-(U$1A-GPIO_45-PadP8.11)") (class "Default")
      (node (ref "U$1") (pin "P8.11") (pinfunction "GPIO_45_P8.11") (pintype "bidirectional"))
    )
    (net (code "55") (name "unconnected-(U$1A-GPIO_46-PadP8.16)") (class "Default")
      (node (ref "U$1") (pin "P8.16") (pinfunction "GPIO_46_P8.16") (pintype "bidirectional"))
    )
    (net (code "56") (name "unconnected-(U$1A-GPIO_47-PadP8.15)") (class "Default")
      (node (ref "U$1") (pin "P8.15") (pinfunction "GPIO_47_P8.15") (pintype "bidirectional"))
    )
    (net (code "57") (name "unconnected-(U$1A-GPIO_61-PadP8.26)") (class "Default")
      (node (ref "U$1") (pin "P8.26") (pinfunction "GPIO_61_P8.26") (pintype "bidirectional"))
    )
    (net (code "58") (name "unconnected-(U$1A-GPIO_62-PadP8.21)") (class "Default")
      (node (ref "U$1") (pin "P8.21") (pinfunction "GPIO_62_P8.21") (pintype "bidirectional"))
    )
    (net (code "59") (name "unconnected-(U$1A-GPIO_63-PadP8.20)") (class "Default")
      (node (ref "U$1") (pin "P8.20") (pinfunction "GPIO_63_P8.20") (pintype "bidirectional"))
    )
    (net (code "60") (name "unconnected-(U$1A-GPIO_65-PadP8.18)") (class "Default")
      (node (ref "U$1") (pin "P8.18") (pinfunction "GPIO_65_P8.18") (pintype "bidirectional"))
    )
    (net (code "61") (name "unconnected-(U$1A-GPIO_66-PadP8.7)") (class "Default")
      (node (ref "U$1") (pin "P8.7") (pinfunction "GPIO_66_P8.7") (pintype "bidirectional"))
    )
    (net (code "62") (name "unconnected-(U$1A-GPIO_67-PadP8.8)") (class "Default")
      (node (ref "U$1") (pin "P8.8") (pinfunction "GPIO_67_P8.8") (pintype "bidirectional"))
    )
    (net (code "63") (name "unconnected-(U$1A-GPIO_68-PadP8.10)") (class "Default")
      (node (ref "U$1") (pin "P8.10") (pinfunction "GPIO_68_P8.10") (pintype "bidirectional"))
    )
    (net (code "64") (name "unconnected-(U$1A-GPIO_69-PadP8.9)") (class "Default")
      (node (ref "U$1") (pin "P8.9") (pinfunction "GPIO_69_P8.9") (pintype "bidirectional"))
    )
    (net (code "65") (name "unconnected-(U$1A-GPIO_70-PadP8.45)") (class "Default")
      (node (ref "U$1") (pin "P8.45") (pinfunction "GPIO_70_P8.45") (pintype "bidirectional"))
    )
    (net (code "66") (name "unconnected-(U$1A-GPIO_71-PadP8.46)") (class "Default")
      (node (ref "U$1") (pin "P8.46") (pinfunction "GPIO_71_P8.46") (pintype "bidirectional"))
    )
    (net (code "67") (name "unconnected-(U$1A-GPIO_72-PadP8.43)") (class "Default")
      (node (ref "U$1") (pin "P8.43") (pinfunction "GPIO_72_P8.43") (pintype "bidirectional"))
    )
    (net (code "68") (name "unconnected-(U$1A-GPIO_73-PadP8.44)") (class "Default")
      (node (ref "U$1") (pin "P8.44") (pinfunction "GPIO_73_P8.44") (pintype "bidirectional"))
    )
    (net (code "69") (name "unconnected-(U$1A-GPIO_74-PadP8.41)") (class "Default")
      (node (ref "U$1") (pin "P8.41") (pinfunction "GPIO_74_P8.41") (pintype "bidirectional"))
    )
    (net (code "70") (name "unconnected-(U$1A-GPIO_75-PadP8.42)") (class "Default")
      (node (ref "U$1") (pin "P8.42") (pinfunction "GPIO_75_P8.42") (pintype "bidirectional"))
    )
    (net (code "71") (name "unconnected-(U$1A-GPIO_76-PadP8.39)") (class "Default")
      (node (ref "U$1") (pin "P8.39") (pinfunction "GPIO_76_P8.39") (pintype "bidirectional"))
    )
    (net (code "72") (name "unconnected-(U$1A-GPIO_77-PadP8.40)") (class "Default")
      (node (ref "U$1") (pin "P8.40") (pinfunction "GPIO_77_P8.40") (pintype "bidirectional"))
    )
    (net (code "73") (name "unconnected-(U$1A-GPIO_78-PadP8.37)") (class "Default")
      (node (ref "U$1") (pin "P8.37") (pinfunction "GPIO_78_P8.37") (pintype "bidirectional"))
    )
    (net (code "74") (name "unconnected-(U$1A-GPIO_79-PadP8.38)") (class "Default")
      (node (ref "U$1") (pin "P8.38") (pinfunction "GPIO_79_P8.38") (pintype "bidirectional"))
    )
    (net (code "75") (name "unconnected-(U$1A-GPIO_80-PadP8.36)") (class "Default")
      (node (ref "U$1") (pin "P8.36") (pinfunction "GPIO_80_P8.36") (pintype "bidirectional"))
    )
    (net (code "76") (name "unconnected-(U$1A-GPIO_81-PadP8.34)") (class "Default")
      (node (ref "U$1") (pin "P8.34") (pinfunction "GPIO_81_P8.34") (pintype "bidirectional"))
    )
    (net (code "77") (name "unconnected-(U$1A-GPIO_86-PadP8.27)") (class "Default")
      (node (ref "U$1") (pin "P8.27") (pinfunction "GPIO_86_P8.27") (pintype "bidirectional"))
    )
    (net (code "78") (name "unconnected-(U$1A-GPIO_87-PadP8.29)") (class "Default")
      (node (ref "U$1") (pin "P8.29") (pinfunction "GPIO_87_P8.29") (pintype "bidirectional"))
    )
    (net (code "79") (name "unconnected-(U$1A-GPIO_88-PadP8.28)") (class "Default")
      (node (ref "U$1") (pin "P8.28") (pinfunction "GPIO_88_P8.28") (pintype "bidirectional"))
    )
    (net (code "80") (name "unconnected-(U$1A-GPIO_89-PadP8.30)") (class "Default")
      (node (ref "U$1") (pin "P8.30") (pinfunction "GPIO_89_P8.30") (pintype "bidirectional"))
    )
    (net (code "81") (name "unconnected-(U$1B-AIN0-PadP9.39)") (class "Default")
      (node (ref "U$1") (pin "P9.39") (pinfunction "AIN0_P9.39") (pintype "bidirectional"))
    )
    (net (code "82") (name "unconnected-(U$1B-AIN1-PadP9.40)") (class "Default")
      (node (ref "U$1") (pin "P9.40") (pinfunction "AIN1_P9.40") (pintype "bidirectional"))
    )
    (net (code "83") (name "unconnected-(U$1B-AIN2-PadP9.37)") (class "Default")
      (node (ref "U$1") (pin "P9.37") (pinfunction "AIN2_P9.37") (pintype "bidirectional"))
    )
    (net (code "84") (name "unconnected-(U$1B-AIN3-PadP9.38)") (class "Default")
      (node (ref "U$1") (pin "P9.38") (pinfunction "AIN3_P9.38") (pintype "bidirectional"))
    )
    (net (code "85") (name "unconnected-(U$1B-AIN4-PadP9.33)") (class "Default")
      (node (ref "U$1") (pin "P9.33") (pinfunction "AIN4_P9.33") (pintype "bidirectional"))
    )
    (net (code "86") (name "unconnected-(U$1B-AIN5-PadP9.36)") (class "Default")
      (node (ref "U$1") (pin "P9.36") (pinfunction "AIN5_P9.36") (pintype "bidirectional"))
    )
    (net (code "87") (name "unconnected-(U$1B-AIN6-PadP9.35)") (class "Default")
      (node (ref "U$1") (pin "P9.35") (pinfunction "AIN6_P9.35") (pintype "bidirectional"))
    )
    (net (code "88") (name "unconnected-(U$1B-GNDA_ADC-PadP9.34)") (class "Default")
      (node (ref "U$1") (pin "P9.34") (pinfunction "GNDA_ADC_P9.34") (pintype "bidirectional"))
    )
    (net (code "89") (name "unconnected-(U$1B-GPIO_2-PadP9.22)") (class "Default")
      (node (ref "U$1") (pin "P9.22") (pinfunction "GPIO_2_P9.22") (pintype "bidirectional"))
    )
    (net (code "90") (name "unconnected-(U$1B-GPIO_3-PadP9.21)") (class "Default")
      (node (ref "U$1") (pin "P9.21") (pinfunction "GPIO_3_P9.21") (pintype "bidirectional"))
    )
    (net (code "91") (name "unconnected-(U$1B-GPIO_4-PadP9.17)") (class "Default")
      (node (ref "U$1") (pin "P9.17") (pinfunction "GPIO_4_P9.17") (pintype "bidirectional"))
    )
    (net (code "92") (name "unconnected-(U$1B-GPIO_5-PadP9.18)") (class "Default")
      (node (ref "U$1") (pin "P9.18") (pinfunction "GPIO_5_P9.18") (pintype "bidirectional"))
    )
    (net (code "93") (name "unconnected-(U$1B-GPIO_7-PadP9.42)") (class "Default")
      (node (ref "U$1") (pin "P9.42") (pinfunction "GPIO_7_P9.42") (pintype "bidirectional"))
    )
    (net (code "94") (name "unconnected-(U$1B-GPIO_14-PadP9.26)") (class "Default")
      (node (ref "U$1") (pin "P9.26") (pinfunction "GPIO_14_P9.26") (pintype "bidirectional"))
    )
    (net (code "95") (name "unconnected-(U$1B-GPIO_15-PadP9.24)") (class "Default")
      (node (ref "U$1") (pin "P9.24") (pinfunction "GPIO_15_P9.24") (pintype "bidirectional"))
    )
    (net (code "96") (name "unconnected-(U$1B-GPIO_30-PadP9.11)") (class "Default")
      (node (ref "U$1") (pin "P9.11") (pinfunction "GPIO_30_P9.11") (pintype "bidirectional"))
    )
    (net (code "97") (name "unconnected-(U$1B-GPIO_31-PadP9.13)") (class "Default")
      (node (ref "U$1") (pin "P9.13") (pinfunction "GPIO_31_P9.13") (pintype "bidirectional"))
    )
    (net (code "98") (name "unconnected-(U$1B-GPIO_40-PadP9.14)") (class "Default")
      (node (ref "U$1") (pin "P9.14") (pinfunction "GPIO_40_P9.14") (pintype "bidirectional"))
    )
    (net (code "99") (name "unconnected-(U$1B-GPIO_48-PadP9.15)") (class "Default")
      (node (ref "U$1") (pin "P9.15") (pinfunction "GPIO_48_P9.15") (pintype "bidirectional"))
    )
    (net (code "100") (name "unconnected-(U$1B-GPIO_49-PadP9.23)") (class "Default")
      (node (ref "U$1") (pin "P9.23") (pinfunction "GPIO_49_P9.23") (pintype "bidirectional"))
    )
    (net (code "101") (name "unconnected-(U$1B-GPIO_51-PadP9.16)") (class "Default")
      (node (ref "U$1") (pin "P9.16") (pinfunction "GPIO_51_P9.16") (pintype "bidirectional"))
    )
    (net (code "102") (name "unconnected-(U$1B-GPIO_60-PadP9.12)") (class "Default")
      (node (ref "U$1") (pin "P9.12") (pinfunction "GPIO_60_P9.12") (pintype "bidirectional"))
    )
    (net (code "103") (name "unconnected-(U$1B-GPIO_122-PadP9.30)") (class "Default")
      (node (ref "U$1") (pin "P9.30") (pinfunction "GPIO_122_P9.30") (pintype "bidirectional"))
    )
    (net (code "104") (name "unconnected-(U$1B-GPIO_125-PadP9.27)") (class "Default")
      (node (ref "U$1") (pin "P9.27") (pinfunction "GPIO_125_P9.27") (pintype "bidirectional"))
    )
    (net (code "105") (name "unconnected-(U$1B-PWR_BUT-PadP9.9)") (class "Default")
      (node (ref "U$1") (pin "P9.9") (pinfunction "PWR_BUT_P9.9") (pintype "bidirectional"))
    )
    (net (code "106") (name "unconnected-(U$1B-SYS_5V-PadP9.7)") (class "Default")
      (node (ref "U$1") (pin "P9.7") (pinfunction "SYS_5V_P9.7") (pintype "bidirectional"))
    )
    (net (code "107") (name "unconnected-(U$1B-SYS_5V-PadP9.8)") (class "Default")
      (node (ref "U$1") (pin "P9.8") (pinfunction "SYS_5V_P9.8") (pintype "bidirectional"))
    )
    (net (code "108") (name "unconnected-(U$1B-SYS_RESET~{N}-PadP9.10)") (class "Default")
      (node (ref "U$1") (pin "P9.10") (pinfunction "SYS_RESET~{N}_P9.10") (pintype "bidirectional"))
    )
    (net (code "109") (name "unconnected-(U$1B-VDD_ADC-PadP9.32)") (class "Default")
      (node (ref "U$1") (pin "P9.32") (pinfunction "VDD_ADC_P9.32") (pintype "bidirectional"))
    )
    (net (code "110") (name "unconnected-(U2-VOUTL--Pad19)") (class "Default")
      (node (ref "U2") (pin "19") (pinfunction "VOUTL-_19") (pintype "output"))
    )
    (net (code "111") (name "unconnected-(U2-VOUTR--Pad17)") (class "Default")
      (node (ref "U2") (pin "17") (pinfunction "VOUTR-_17") (pintype "output"))
    )
    (net (code "112") (name "unconnected-(U2-ZEROL-Pad14)") (class "Default")
      (node (ref "U2") (pin "14") (pinfunction "ZEROL_14") (pintype "output"))
    )
    (net (code "113") (name "unconnected-(U2-ZEROR-Pad12)") (class "Default")
      (node (ref "U2") (pin "12") (pinfunction "ZEROR_12") (pintype "output"))
    )
    (net (code "114") (name "unconnected-(U3-GAIN-Pad1)") (class "Default")
      (node (ref "U3") (pin "1") (pinfunction "GAIN_1") (pintype "bidirectional"))
    )
    (net (code "115") (name "unconnected-(U3-GAIN-Pad8)") (class "Default")
      (node (ref "U3") (pin "8") (pinfunction "GAIN_8") (pintype "bidirectional"))
    )
  )
)
